# ICS-RS232C_Converter.net
KiCad netlist of a schematic drawn in EAGLE
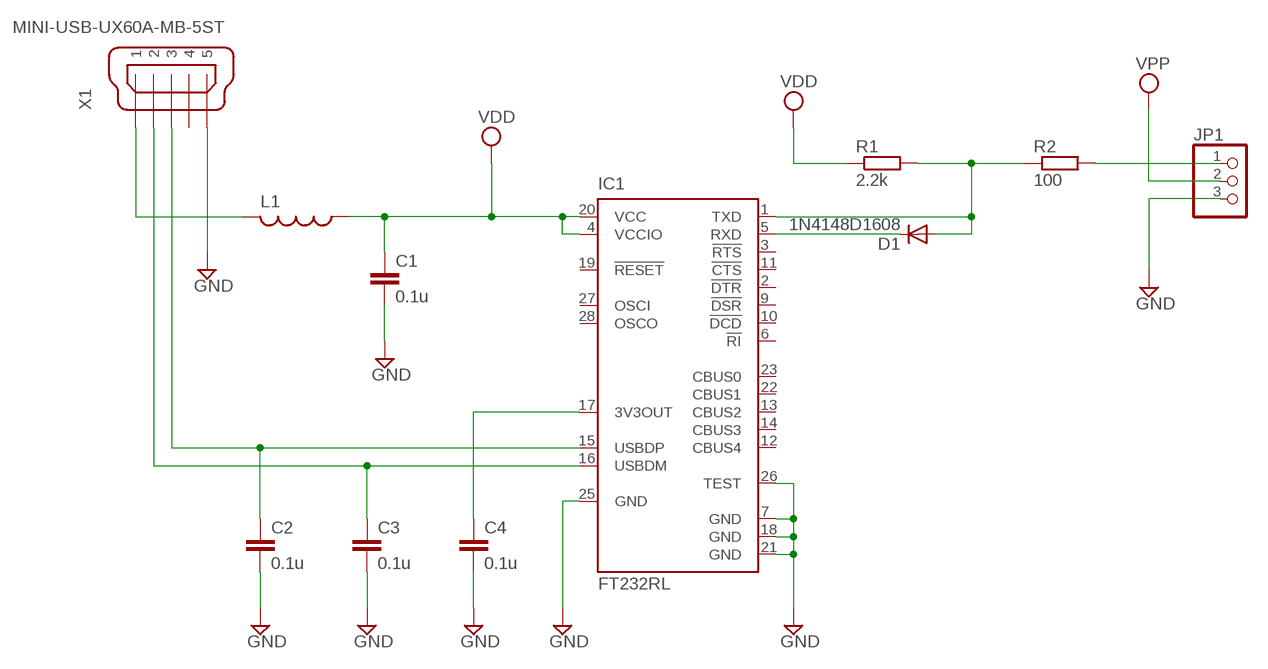
[diagram p0: schematic, sheet 1]

(export (version "E")
  (design (tool "Eeschema 10.0.6"))
  (components
    (comp (ref "C1")
      (value "0.1u")
      (footprint "eagle-import:C1608")
      (libsource (lib "eagle-import") (part "C-EUC1608"))
    )
    (comp (ref "C2")
      (value "0.1u")
      (footprint "eagle-import:C1608")
      (libsource (lib "eagle-import") (part "C-EUC1608"))
    )
    (comp (ref "C3")
      (value "0.1u")
      (footprint "eagle-import:C1608")
      (libsource (lib "eagle-import") (part "C-EUC1608"))
    )
    (comp (ref "C4")
      (value "0.1u")
      (footprint "eagle-import:C1608")
      (libsource (lib "eagle-import") (part "C-EUC1608"))
    )
    (comp (ref "D1")
      (value "1N4148D1608")
      (footprint "eagle-import:D1608")
      (libsource (lib "eagle-import") (part "1N4148D1608"))
    )
    (comp (ref "IC1")
      (value "FT232RL")
      (footprint "eagle-import:SSOP28")
      (libsource (lib "eagle-import") (part "FT232RL"))
    )
    (comp (ref "JP1")
      (value "PINHD-1X3")
      (footprint "eagle-import:1X03")
      (libsource (lib "eagle-import") (part "PINHD-1X3"))
    )
    (comp (ref "L1")
      (value "L-USL2012C")
      (footprint "eagle-import:L2012C")
      (libsource (lib "eagle-import") (part "L-USL2012C"))
    )
    (comp (ref "R1")
      (value "2.2k")
      (footprint "eagle-import:C1608")
      (libsource (lib "eagle-import") (part "R-EU_R1608"))
    )
    (comp (ref "R2")
      (value "100")
      (footprint "eagle-import:C1608")
      (libsource (lib "eagle-import") (part "R-EU_R1608"))
    )
    (comp (ref "X1")
      (value "MINI-USB-UX60A-MB-5ST")
      (footprint "eagle-import:UX60A-MB-5ST")
      (libsource (lib "eagle-import") (part "MINI-USB-UX60A-MB-5ST"))
    )
  )
  (nets
    (net (code "1") (name "GND") (class "Default")
      (node (ref "C1") (pin "2") (pinfunction "2_2") (pintype "passive"))
      (node (ref "C2") (pin "2") (pinfunction "2_2") (pintype "passive"))
      (node (ref "C3") (pin "2") (pinfunction "2_2") (pintype "passive"))
      (node (ref "C4") (pin "2") (pinfunction "2_2") (pintype "passive"))
      (node (ref "IC1") (pin "18") (pinfunction "GND_18") (pintype "power_in"))
      (node (ref "IC1") (pin "21") (pinfunction "GND_21") (pintype "power_in"))
      (node (ref "IC1") (pin "25") (pinfunction "GND_25") (pintype "power_in"))
      (node (ref "IC1") (pin "26") (pinfunction "TEST_26") (pintype "input"))
      (node (ref "IC1") (pin "7") (pinfunction "GND_7") (pintype "power_in"))
      (node (ref "JP1") (pin "3") (pinfunction "3_3") (pintype "passive"))
      (node (ref "X1") (pin "5") (pinfunction "5_5") (pintype "input"))
    )
    (net (code "2") (name "Net-(D1-A)") (class "Default")
      (node (ref "D1") (pin "1") (pinfunction "A_1") (pintype "passive"))
      (node (ref "IC1") (pin "1") (pinfunction "TXD_1") (pintype "output"))
      (node (ref "R1") (pin "2") (pinfunction "2_2") (pintype "passive"))
      (node (ref "R2") (pin "1") (pinfunction "1_1") (pintype "passive"))
    )
    (net (code "3") (name "Net-(D1-C)") (class "Default")
      (node (ref "D1") (pin "2") (pinfunction "C_2") (pintype "passive"))
      (node (ref "IC1") (pin "5") (pinfunction "RXD_5") (pintype "input"))
    )
    (net (code "4") (name "Net-(IC1-3V3OUT)") (class "Default")
      (node (ref "C4") (pin "1") (pinfunction "1_1") (pintype "passive"))
      (node (ref "IC1") (pin "17") (pinfunction "3V3OUT_17") (pintype "output"))
    )
    (net (code "5") (name "Net-(IC1-USBDM)") (class "Default")
      (node (ref "C3") (pin "1") (pinfunction "1_1") (pintype "passive"))
      (node (ref "IC1") (pin "16") (pinfunction "USBDM_16") (pintype "bidirectional"))
      (node (ref "X1") (pin "2") (pinfunction "2_2") (pintype "input"))
    )
    (net (code "6") (name "Net-(IC1-USBDP)") (class "Default")
      (node (ref "C2") (pin "1") (pinfunction "1_1") (pintype "passive"))
      (node (ref "IC1") (pin "15") (pinfunction "USBDP_15") (pintype "bidirectional"))
      (node (ref "X1") (pin "3") (pinfunction "3_3") (pintype "input"))
    )
    (net (code "7") (name "Net-(JP1-Pad1)") (class "Default")
      (node (ref "JP1") (pin "1") (pinfunction "1_1") (pintype "passive"))
      (node (ref "R2") (pin "2") (pinfunction "2_2") (pintype "passive"))
    )
    (net (code "8") (name "Net-(L1-Pad2)") (class "Default")
      (node (ref "L1") (pin "2") (pinfunction "2_2") (pintype "passive"))
      (node (ref "X1") (pin "1") (pinfunction "1_1") (pintype "input"))
    )
    (net (code "9") (name "VDD") (class "Default")
      (node (ref "C1") (pin "1") (pinfunction "1_1") (pintype "passive"))
      (node (ref "IC1") (pin "20") (pinfunction "VCC_20") (pintype "power_in"))
      (node (ref "IC1") (pin "4") (pinfunction "VCCIO_4") (pintype "power_in"))
      (node (ref "L1") (pin "1") (pinfunction "1_1") (pintype "passive"))
      (node (ref "R1") (pin "1") (pinfunction "1_1") (pintype "passive"))
    )
    (net (code "10") (name "VPP") (class "Default")
      (node (ref "JP1") (pin "2") (pinfunction "2_2") (pintype "passive"))
    )
    (net (code "11") (name "unconnected-(IC1-CBUS0-Pad23)") (class "Default")
      (node (ref "IC1") (pin "23") (pinfunction "CBUS0_23") (pintype "bidirectional"))
    )
    (net (code "12") (name "unconnected-(IC1-CBUS1-Pad22)") (class "Default")
      (node (ref "IC1") (pin "22") (pinfunction "CBUS1_22") (pintype "bidirectional"))
    )
    (net (code "13") (name "unconnected-(IC1-CBUS2-Pad13)") (class "Default")
      (node (ref "IC1") (pin "13") (pinfunction "CBUS2_13") (pintype "bidirectional"))
    )
    (net (code "14") (name "unconnected-(IC1-CBUS3-Pad14)") (class "Default")
      (node (ref "IC1") (pin "14") (pinfunction "CBUS3_14") (pintype "bidirectional"))
    )
    (net (code "15") (name "unconnected-(IC1-CBUS4-Pad12)") (class "Default")
      (node (ref "IC1") (pin "12") (pinfunction "CBUS4_12") (pintype "bidirectional"))
    )
    (net (code "16") (name "unconnected-(IC1-OSCI-Pad27)") (class "Default")
      (node (ref "IC1") (pin "27") (pinfunction "OSCI_27") (pintype "input"))
    )
    (net (code "17") (name "unconnected-(IC1-OSCO-Pad28)") (class "Default")
      (node (ref "IC1") (pin "28") (pinfunction "OSCO_28") (pintype "output"))
    )
    (net (code "18") (name "unconnected-(IC1-~{CTS}-Pad11)") (class "Default")
      (node (ref "IC1") (pin "11") (pinfunction "~{CTS}_11") (pintype "input"))
    )
    (net (code "19") (name "unconnected-(IC1-~{DCD}-Pad10)") (class "Default")
      (node (ref "IC1") (pin "10") (pinfunction "~{DCD}_10") (pintype "input"))
    )
    (net (code "20") (name "unconnected-(IC1-~{DSR}-Pad9)") (class "Default")
      (node (ref "IC1") (pin "9") (pinfunction "~{DSR}_9") (pintype "input"))
    )
    (net (code "21") (name "unconnected-(IC1-~{DTR}-Pad2)") (class "Default")
      (node (ref "IC1") (pin "2") (pinfunction "~{DTR}_2") (pintype "output"))
    )
    (net (code "22") (name "unconnected-(IC1-~{RESET}-Pad19)") (class "Default")
      (node (ref "IC1") (pin "19") (pinfunction "~{RESET}_19") (pintype "input"))
    )
    (net (code "23") (name "unconnected-(IC1-~{RI}-Pad6)") (class "Default")
      (node (ref "IC1") (pin "6") (pinfunction "~{RI}_6") (pintype "input"))
    )
    (net (code "24") (name "unconnected-(IC1-~{RTS}-Pad3)") (class "Default")
      (node (ref "IC1") (pin "3") (pinfunction "~{RTS}_3") (pintype "output"))
    )
    (net (code "25") (name "unconnected-(X1-Pad4)") (class "Default")
      (node (ref "X1") (pin "4") (pinfunction "4_4") (pintype "input"))
    )
  )
)
